# Digital_Input_Board.net
KiCad netlist of a schematic drawn in EAGLE
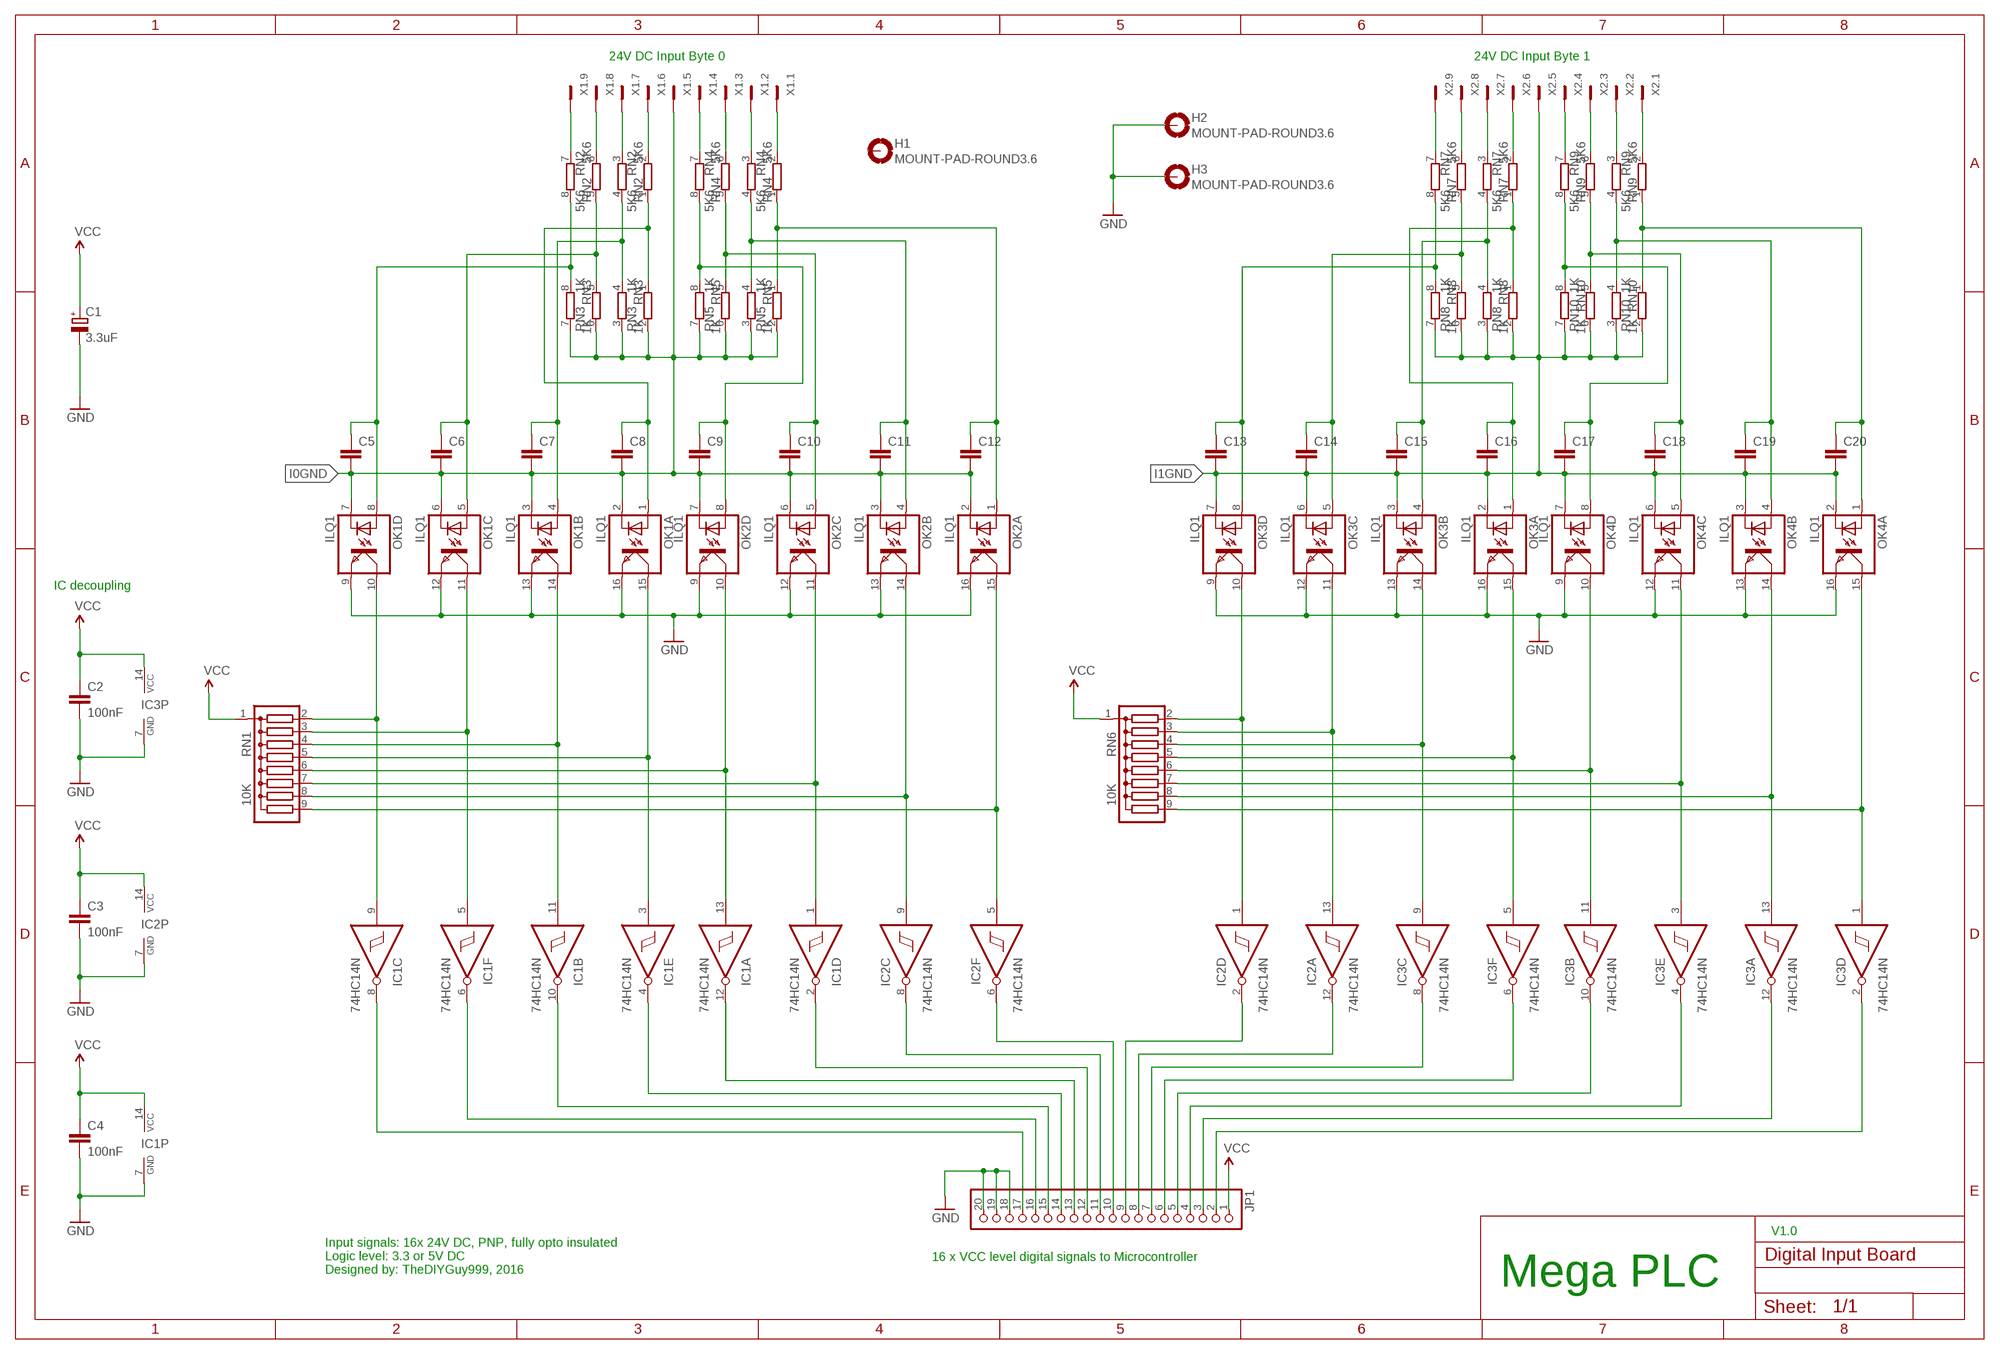
[diagram p0: schematic, sheet 1]

(export (version "E")
  (design (tool "Eeschema 10.0.6"))
  (components
    (comp (ref "C1")
      (value "3.3uF")
      (footprint "eagle-import:B45181A")
      (libsource (lib "eagle-import") (part "CPOL-EUB45181A"))
    )
    (comp (ref "C2")
      (value "100nF")
      (footprint "eagle-import:C025-024X044")
      (libsource (lib "eagle-import") (part "resistor_C-EU025-024X044"))
    )
    (comp (ref "C3")
      (value "100nF")
      (footprint "eagle-import:C025-024X044")
      (libsource (lib "eagle-import") (part "resistor_C-EU025-024X044"))
    )
    (comp (ref "C4")
      (value "100nF")
      (footprint "eagle-import:C025-024X044")
      (libsource (lib "eagle-import") (part "resistor_C-EU025-024X044"))
    )
    (comp (ref "C5")
      (value "C-EUC0805K")
      (footprint "eagle-import:C0805K")
      (libsource (lib "eagle-import") (part "C-EUC0805K"))
    )
    (comp (ref "C6")
      (value "C-EUC0805K")
      (footprint "eagle-import:C0805K")
      (libsource (lib "eagle-import") (part "C-EUC0805K"))
    )
    (comp (ref "C7")
      (value "C-EUC0805K")
      (footprint "eagle-import:C0805K")
      (libsource (lib "eagle-import") (part "C-EUC0805K"))
    )
    (comp (ref "C8")
      (value "C-EUC0805K")
      (footprint "eagle-import:C0805K")
      (libsource (lib "eagle-import") (part "C-EUC0805K"))
    )
    (comp (ref "C9")
      (value "C-EUC0805K")
      (footprint "eagle-import:C0805K")
      (libsource (lib "eagle-import") (part "C-EUC0805K"))
    )
    (comp (ref "C10")
      (value "C-EUC0805K")
      (footprint "eagle-import:C0805K")
      (libsource (lib "eagle-import") (part "C-EUC0805K"))
    )
    (comp (ref "C11")
      (value "C-EUC0805K")
      (footprint "eagle-import:C0805K")
      (libsource (lib "eagle-import") (part "C-EUC0805K"))
    )
    (comp (ref "C12")
      (value "C-EUC0805K")
      (footprint "eagle-import:C0805K")
      (libsource (lib "eagle-import") (part "C-EUC0805K"))
    )
    (comp (ref "C13")
      (value "C-EUC0805K")
      (footprint "eagle-import:C0805K")
      (libsource (lib "eagle-import") (part "C-EUC0805K"))
    )
    (comp (ref "C14")
      (value "C-EUC0805K")
      (footprint "eagle-import:C0805K")
      (libsource (lib "eagle-import") (part "C-EUC0805K"))
    )
    (comp (ref "C15")
      (value "C-EUC0805K")
      (footprint "eagle-import:C0805K")
      (libsource (lib "eagle-import") (part "C-EUC0805K"))
    )
    (comp (ref "C16")
      (value "C-EUC0805K")
      (footprint "eagle-import:C0805K")
      (libsource (lib "eagle-import") (part "C-EUC0805K"))
    )
    (comp (ref "C17")
      (value "C-EUC0805K")
      (footprint "eagle-import:C0805K")
      (libsource (lib "eagle-import") (part "C-EUC0805K"))
    )
    (comp (ref "C18")
      (value "C-EUC0805K")
      (footprint "eagle-import:C0805K")
      (libsource (lib "eagle-import") (part "C-EUC0805K"))
    )
    (comp (ref "C19")
      (value "C-EUC0805K")
      (footprint "eagle-import:C0805K")
      (libsource (lib "eagle-import") (part "C-EUC0805K"))
    )
    (comp (ref "C20")
      (value "C-EUC0805K")
      (footprint "eagle-import:C0805K")
      (libsource (lib "eagle-import") (part "C-EUC0805K"))
    )
    (comp (ref "H1")
      (value "MOUNT-PAD-ROUND3.6")
      (footprint "eagle-import:3,6-PAD")
      (libsource (lib "eagle-import") (part "MOUNT-PAD-ROUND3.6"))
    )
    (comp (ref "H2")
      (value "MOUNT-PAD-ROUND3.6")
      (footprint "eagle-import:3,6-PAD")
      (libsource (lib "eagle-import") (part "MOUNT-PAD-ROUND3.6"))
    )
    (comp (ref "H3")
      (value "MOUNT-PAD-ROUND3.6")
      (footprint "eagle-import:3,6-PAD")
      (libsource (lib "eagle-import") (part "MOUNT-PAD-ROUND3.6"))
    )
    (comp (ref "IC1")
      (value "74HC14N")
      (footprint "eagle-import:DIL14")
      (libsource (lib "eagle-import") (part "7414NHC"))
    )
    (comp (ref "IC2")
      (value "74HC14N")
      (footprint "eagle-import:DIL14")
      (libsource (lib "eagle-import") (part "7414NHC"))
    )
    (comp (ref "IC3")
      (value "74HC14N")
      (footprint "eagle-import:DIL14")
      (libsource (lib "eagle-import") (part "7414NHC"))
    )
    (comp (ref "JP1")
      (value "PINHD-1X20/90")
      (footprint "eagle-import:1X20_90")
      (libsource (lib "eagle-import") (part "PINHD-1X20/90"))
    )
    (comp (ref "OK1")
      (value "ILQ1")
      (footprint "eagle-import:DIL16")
      (fields (field (name "MF") "VISHAY/TELEFUNKEN"))
      (libsource (lib "eagle-import") (part "ILQ1"))
    )
    (comp (ref "OK2")
      (value "ILQ1")
      (footprint "eagle-import:DIL16")
      (fields (field (name "MF") "VISHAY/TELEFUNKEN"))
      (libsource (lib "eagle-import") (part "ILQ1"))
    )
    (comp (ref "OK3")
      (value "ILQ1")
      (footprint "eagle-import:DIL16")
      (fields (field (name "MF") "VISHAY/TELEFUNKEN"))
      (libsource (lib "eagle-import") (part "ILQ1"))
    )
    (comp (ref "OK4")
      (value "ILQ1")
      (footprint "eagle-import:DIL16")
      (fields (field (name "MF") "VISHAY/TELEFUNKEN"))
      (libsource (lib "eagle-import") (part "ILQ1"))
    )
    (comp (ref "RN1")
      (value "10K")
      (footprint "eagle-import:SIL9")
      (libsource (lib "eagle-import") (part "G08R"))
    )
    (comp (ref "RN2")
      (value "5K6")
      (footprint "eagle-import:SIL8")
      (libsource (lib "eagle-import") (part "E4RP"))
    )
    (comp (ref "RN3")
      (value "1K")
      (footprint "eagle-import:SIL8")
      (libsource (lib "eagle-import") (part "E4RP"))
    )
    (comp (ref "RN4")
      (value "5K6")
      (footprint "eagle-import:SIL8")
      (libsource (lib "eagle-import") (part "E4RP"))
    )
    (comp (ref "RN5")
      (value "1K")
      (footprint "eagle-import:SIL8")
      (libsource (lib "eagle-import") (part "E4RP"))
    )
    (comp (ref "RN6")
      (value "10K")
      (footprint "eagle-import:SIL9")
      (libsource (lib "eagle-import") (part "G08R"))
    )
    (comp (ref "RN7")
      (value "5K6")
      (footprint "eagle-import:SIL8")
      (libsource (lib "eagle-import") (part "E4RP"))
    )
    (comp (ref "RN8")
      (value "1K")
      (footprint "eagle-import:SIL8")
      (libsource (lib "eagle-import") (part "E4RP"))
    )
    (comp (ref "RN9")
      (value "5K6")
      (footprint "eagle-import:SIL8")
      (libsource (lib "eagle-import") (part "E4RP"))
    )
    (comp (ref "RN10")
      (value "1K")
      (footprint "eagle-import:SIL8")
      (libsource (lib "eagle-import") (part "E4RP"))
    )
    (comp (ref "X1")
      (value "MC9")
      (footprint "eagle-import:MC9")
      (libsource (lib "eagle-import") (part "MC9"))
    )
    (comp (ref "X2")
      (value "MC9")
      (footprint "eagle-import:MC9")
      (libsource (lib "eagle-import") (part "MC9"))
    )
  )
  (nets
    (net (code "1") (name "GND") (class "Default")
      (node (ref "C1") (pin "-") (pinfunction "-_-") (pintype "passive"))
      (node (ref "C2") (pin "2") (pinfunction "2_2") (pintype "passive"))
      (node (ref "C3") (pin "2") (pinfunction "2_2") (pintype "passive"))
      (node (ref "C4") (pin "2") (pinfunction "2_2") (pintype "passive"))
      (node (ref "H2") (pin "B3,6") (pinfunction "MOUNT_B3,6") (pintype "passive"))
      (node (ref "H3") (pin "B3,6") (pinfunction "MOUNT_B3,6") (pintype "passive"))
      (node (ref "IC1") (pin "7") (pinfunction "GND_7") (pintype "power_in"))
      (node (ref "IC2") (pin "7") (pinfunction "GND_7") (pintype "power_in"))
      (node (ref "IC3") (pin "7") (pinfunction "GND_7") (pintype "power_in"))
      (node (ref "JP1") (pin "18") (pinfunction "18_18") (pintype "passive"))
      (node (ref "JP1") (pin "19") (pinfunction "19_19") (pintype "passive"))
      (node (ref "JP1") (pin "20") (pinfunction "20_20") (pintype "passive"))
      (node (ref "OK1") (pin "12") (pinfunction "EMIT_12") (pintype "passive"))
      (node (ref "OK1") (pin "13") (pinfunction "EMIT_13") (pintype "passive"))
      (node (ref "OK1") (pin "16") (pinfunction "EMIT_16") (pintype "passive"))
      (node (ref "OK1") (pin "9") (pinfunction "EMIT_9") (pintype "passive"))
      (node (ref "OK2") (pin "12") (pinfunction "EMIT_12") (pintype "passive"))
      (node (ref "OK2") (pin "13") (pinfunction "EMIT_13") (pintype "passive"))
      (node (ref "OK2") (pin "16") (pinfunction "EMIT_16") (pintype "passive"))
      (node (ref "OK2") (pin "9") (pinfunction "EMIT_9") (pintype "passive"))
      (node (ref "OK3") (pin "12") (pinfunction "EMIT_12") (pintype "passive"))
      (node (ref "OK3") (pin "13") (pinfunction "EMIT_13") (pintype "passive"))
      (node (ref "OK3") (pin "16") (pinfunction "EMIT_16") (pintype "passive"))
      (node (ref "OK3") (pin "9") (pinfunction "EMIT_9") (pintype "passive"))
      (node (ref "OK4") (pin "12") (pinfunction "EMIT_12") (pintype "passive"))
      (node (ref "OK4") (pin "13") (pinfunction "EMIT_13") (pintype "passive"))
      (node (ref "OK4") (pin "16") (pinfunction "EMIT_16") (pintype "passive"))
      (node (ref "OK4") (pin "9") (pinfunction "EMIT_9") (pintype "passive"))
    )
    (net (code "2") (name "I0GND") (class "Default")
      (node (ref "C10") (pin "2") (pinfunction "2_2") (pintype "passive"))
      (node (ref "C11") (pin "2") (pinfunction "2_2") (pintype "passive"))
      (node (ref "C12") (pin "2") (pinfunction "2_2") (pintype "passive"))
      (node (ref "C5") (pin "2") (pinfunction "2_2") (pintype "passive"))
      (node (ref "C6") (pin "2") (pinfunction "2_2") (pintype "passive"))
      (node (ref "C7") (pin "2") (pinfunction "2_2") (pintype "passive"))
      (node (ref "C8") (pin "2") (pinfunction "2_2") (pintype "passive"))
      (node (ref "C9") (pin "2") (pinfunction "2_2") (pintype "passive"))
      (node (ref "OK1") (pin "2") (pinfunction "C_2") (pintype "passive"))
      (node (ref "OK1") (pin "3") (pinfunction "C_3") (pintype "passive"))
      (node (ref "OK1") (pin "6") (pinfunction "C_6") (pintype "passive"))
      (node (ref "OK1") (pin "7") (pinfunction "C_7") (pintype "passive"))
      (node (ref "OK2") (pin "2") (pinfunction "C_2") (pintype "passive"))
      (node (ref "OK2") (pin "3") (pinfunction "C_3") (pintype "passive"))
      (node (ref "OK2") (pin "6") (pinfunction "C_6") (pintype "passive"))
      (node (ref "OK2") (pin "7") (pinfunction "C_7") (pintype "passive"))
      (node (ref "RN3") (pin "2") (pinfunction "2_2") (pintype "passive"))
      (node (ref "RN3") (pin "3") (pinfunction "1_3") (pintype "passive"))
      (node (ref "RN3") (pin "6") (pinfunction "2_6") (pintype "passive"))
      (node (ref "RN3") (pin "7") (pinfunction "1_7") (pintype "passive"))
      (node (ref "RN5") (pin "2") (pinfunction "2_2") (pintype "passive"))
      (node (ref "RN5") (pin "3") (pinfunction "1_3") (pintype "passive"))
      (node (ref "RN5") (pin "6") (pinfunction "2_6") (pintype "passive"))
      (node (ref "RN5") (pin "7") (pinfunction "1_7") (pintype "passive"))
      (node (ref "X1") (pin "5") (pinfunction "SK_5") (pintype "passive"))
    )
    (net (code "3") (name "I1GND") (class "Default")
      (node (ref "C13") (pin "2") (pinfunction "2_2") (pintype "passive"))
      (node (ref "C14") (pin "2") (pinfunction "2_2") (pintype "passive"))
      (node (ref "C15") (pin "2") (pinfunction "2_2") (pintype "passive"))
      (node (ref "C16") (pin "2") (pinfunction "2_2") (pintype "passive"))
      (node (ref "C17") (pin "2") (pinfunction "2_2") (pintype "passive"))
      (node (ref "C18") (pin "2") (pinfunction "2_2") (pintype "passive"))
      (node (ref "C19") (pin "2") (pinfunction "2_2") (pintype "passive"))
      (node (ref "C20") (pin "2") (pinfunction "2_2") (pintype "passive"))
      (node (ref "OK3") (pin "2") (pinfunction "C_2") (pintype "passive"))
      (node (ref "OK3") (pin "3") (pinfunction "C_3") (pintype "passive"))
      (node (ref "OK3") (pin "6") (pinfunction "C_6") (pintype "passive"))
      (node (ref "OK3") (pin "7") (pinfunction "C_7") (pintype "passive"))
      (node (ref "OK4") (pin "2") (pinfunction "C_2") (pintype "passive"))
      (node (ref "OK4") (pin "3") (pinfunction "C_3") (pintype "passive"))
      (node (ref "OK4") (pin "6") (pinfunction "C_6") (pintype "passive"))
      (node (ref "OK4") (pin "7") (pinfunction "C_7") (pintype "passive"))
      (node (ref "RN10") (pin "2") (pinfunction "2_2") (pintype "passive"))
      (node (ref "RN10") (pin "3") (pinfunction "1_3") (pintype "passive"))
      (node (ref "RN10") (pin "6") (pinfunction "2_6") (pintype "passive"))
      (node (ref "RN10") (pin "7") (pinfunction "1_7") (pintype "passive"))
      (node (ref "RN8") (pin "2") (pinfunction "2_2") (pintype "passive"))
      (node (ref "RN8") (pin "3") (pinfunction "1_3") (pintype "passive"))
      (node (ref "RN8") (pin "6") (pinfunction "2_6") (pintype "passive"))
      (node (ref "RN8") (pin "7") (pinfunction "1_7") (pintype "passive"))
      (node (ref "X2") (pin "5") (pinfunction "SK_5") (pintype "passive"))
    )
    (net (code "4") (name "Net-(IC1A-I)") (class "Default")
      (node (ref "IC1") (pin "13") (pinfunction "I_13") (pintype "input"))
      (node (ref "OK2") (pin "10") (pinfunction "COL_10") (pintype "passive"))
      (node (ref "RN1") (pin "6") (pinfunction "6_6") (pintype "passive"))
    )
    (net (code "5") (name "Net-(IC1A-O)") (class "Default")
      (node (ref "IC1") (pin "12") (pinfunction "O_12") (pintype "output"))
      (node (ref "JP1") (pin "13") (pinfunction "13_13") (pintype "passive"))
    )
    (net (code "6") (name "Net-(IC1B-I)") (class "Default")
      (node (ref "IC1") (pin "11") (pinfunction "I_11") (pintype "input"))
      (node (ref "OK1") (pin "14") (pinfunction "COL_14") (pintype "passive"))
      (node (ref "RN1") (pin "4") (pinfunction "4_4") (pintype "passive"))
    )
    (net (code "7") (name "Net-(IC1B-O)") (class "Default")
      (node (ref "IC1") (pin "10") (pinfunction "O_10") (pintype "output"))
      (node (ref "JP1") (pin "15") (pinfunction "15_15") (pintype "passive"))
    )
    (net (code "8") (name "Net-(IC1C-I)") (class "Default")
      (node (ref "IC1") (pin "9") (pinfunction "I_9") (pintype "input"))
      (node (ref "OK1") (pin "10") (pinfunction "COL_10") (pintype "passive"))
      (node (ref "RN1") (pin "2") (pinfunction "2_2") (pintype "passive"))
    )
    (net (code "9") (name "Net-(IC1C-O)") (class "Default")
      (node (ref "IC1") (pin "8") (pinfunction "O_8") (pintype "output"))
      (node (ref "JP1") (pin "17") (pinfunction "17_17") (pintype "passive"))
    )
    (net (code "10") (name "Net-(IC1D-I)") (class "Default")
      (node (ref "IC1") (pin "1") (pinfunction "I_1") (pintype "input"))
      (node (ref "OK2") (pin "11") (pinfunction "COL_11") (pintype "passive"))
      (node (ref "RN1") (pin "7") (pinfunction "7_7") (pintype "passive"))
    )
    (net (code "11") (name "Net-(IC1D-O)") (class "Default")
      (node (ref "IC1") (pin "2") (pinfunction "O_2") (pintype "output"))
      (node (ref "JP1") (pin "12") (pinfunction "12_12") (pintype "passive"))
    )
    (net (code "12") (name "Net-(IC1E-I)") (class "Default")
      (node (ref "IC1") (pin "3") (pinfunction "I_3") (pintype "input"))
      (node (ref "OK1") (pin "15") (pinfunction "COL_15") (pintype "passive"))
      (node (ref "RN1") (pin "5") (pinfunction "5_5") (pintype "passive"))
    )
    (net (code "13") (name "Net-(IC1E-O)") (class "Default")
      (node (ref "IC1") (pin "4") (pinfunction "O_4") (pintype "output"))
      (node (ref "JP1") (pin "14") (pinfunction "14_14") (pintype "passive"))
    )
    (net (code "14") (name "Net-(IC1F-I)") (class "Default")
      (node (ref "IC1") (pin "5") (pinfunction "I_5") (pintype "input"))
      (node (ref "OK1") (pin "11") (pinfunction "COL_11") (pintype "passive"))
      (node (ref "RN1") (pin "3") (pinfunction "3_3") (pintype "passive"))
    )
    (net (code "15") (name "Net-(IC1F-O)") (class "Default")
      (node (ref "IC1") (pin "6") (pinfunction "O_6") (pintype "output"))
      (node (ref "JP1") (pin "16") (pinfunction "16_16") (pintype "passive"))
    )
    (net (code "16") (name "Net-(IC2A-I)") (class "Default")
      (node (ref "IC2") (pin "13") (pinfunction "I_13") (pintype "input"))
      (node (ref "OK3") (pin "11") (pinfunction "COL_11") (pintype "passive"))
      (node (ref "RN6") (pin "3") (pinfunction "3_3") (pintype "passive"))
    )
    (net (code "17") (name "Net-(IC2A-O)") (class "Default")
      (node (ref "IC2") (pin "12") (pinfunction "O_12") (pintype "output"))
      (node (ref "JP1") (pin "8") (pinfunction "8_8") (pintype "passive"))
    )
    (net (code "18") (name "Net-(IC2C-I)") (class "Default")
      (node (ref "IC2") (pin "9") (pinfunction "I_9") (pintype "input"))
      (node (ref "OK2") (pin "14") (pinfunction "COL_14") (pintype "passive"))
      (node (ref "RN1") (pin "8") (pinfunction "8_8") (pintype "passive"))
    )
    (net (code "19") (name "Net-(IC2C-O)") (class "Default")
      (node (ref "IC2") (pin "8") (pinfunction "O_8") (pintype "output"))
      (node (ref "JP1") (pin "11") (pinfunction "11_11") (pintype "passive"))
    )
    (net (code "20") (name "Net-(IC2D-I)") (class "Default")
      (node (ref "IC2") (pin "1") (pinfunction "I_1") (pintype "input"))
      (node (ref "OK3") (pin "10") (pinfunction "COL_10") (pintype "passive"))
      (node (ref "RN6") (pin "2") (pinfunction "2_2") (pintype "passive"))
    )
    (net (code "21") (name "Net-(IC2D-O)") (class "Default")
      (node (ref "IC2") (pin "2") (pinfunction "O_2") (pintype "output"))
      (node (ref "JP1") (pin "9") (pinfunction "9_9") (pintype "passive"))
    )
    (net (code "22") (name "Net-(IC2F-I)") (class "Default")
      (node (ref "IC2") (pin "5") (pinfunction "I_5") (pintype "input"))
      (node (ref "OK2") (pin "15") (pinfunction "COL_15") (pintype "passive"))
      (node (ref "RN1") (pin "9") (pinfunction "9_9") (pintype "passive"))
    )
    (net (code "23") (name "Net-(IC2F-O)") (class "Default")
      (node (ref "IC2") (pin "6") (pinfunction "O_6") (pintype "output"))
      (node (ref "JP1") (pin "10") (pinfunction "10_10") (pintype "passive"))
    )
    (net (code "24") (name "Net-(IC3A-I)") (class "Default")
      (node (ref "IC3") (pin "13") (pinfunction "I_13") (pintype "input"))
      (node (ref "OK4") (pin "14") (pinfunction "COL_14") (pintype "passive"))
      (node (ref "RN6") (pin "8") (pinfunction "8_8") (pintype "passive"))
    )
    (net (code "25") (name "Net-(IC3A-O)") (class "Default")
      (node (ref "IC3") (pin "12") (pinfunction "O_12") (pintype "output"))
      (node (ref "JP1") (pin "3") (pinfunction "3_3") (pintype "passive"))
    )
    (net (code "26") (name "Net-(IC3B-I)") (class "Default")
      (node (ref "IC3") (pin "11") (pinfunction "I_11") (pintype "input"))
      (node (ref "OK4") (pin "10") (pinfunction "COL_10") (pintype "passive"))
      (node (ref "RN6") (pin "6") (pinfunction "6_6") (pintype "passive"))
    )
    (net (code "27") (name "Net-(IC3B-O)") (class "Default")
      (node (ref "IC3") (pin "10") (pinfunction "O_10") (pintype "output"))
      (node (ref "JP1") (pin "5") (pinfunction "5_5") (pintype "passive"))
    )
    (net (code "28") (name "Net-(IC3C-I)") (class "Default")
      (node (ref "IC3") (pin "9") (pinfunction "I_9") (pintype "input"))
      (node (ref "OK3") (pin "14") (pinfunction "COL_14") (pintype "passive"))
      (node (ref "RN6") (pin "4") (pinfunction "4_4") (pintype "passive"))
    )
    (net (code "29") (name "Net-(IC3C-O)") (class "Default")
      (node (ref "IC3") (pin "8") (pinfunction "O_8") (pintype "output"))
      (node (ref "JP1") (pin "7") (pinfunction "7_7") (pintype "passive"))
    )
    (net (code "30") (name "Net-(IC3D-I)") (class "Default")
      (node (ref "IC3") (pin "1") (pinfunction "I_1") (pintype "input"))
      (node (ref "OK4") (pin "15") (pinfunction "COL_15") (pintype "passive"))
      (node (ref "RN6") (pin "9") (pinfunction "9_9") (pintype "passive"))
    )
    (net (code "31") (name "Net-(IC3D-O)") (class "Default")
      (node (ref "IC3") (pin "2") (pinfunction "O_2") (pintype "output"))
      (node (ref "JP1") (pin "2") (pinfunction "2_2") (pintype "passive"))
    )
    (net (code "32") (name "Net-(IC3E-I)") (class "Default")
      (node (ref "IC3") (pin "3") (pinfunction "I_3") (pintype "input"))
      (node (ref "OK4") (pin "11") (pinfunction "COL_11") (pintype "passive"))
      (node (ref "RN6") (pin "7") (pinfunction "7_7") (pintype "passive"))
    )
    (net (code "33") (name "Net-(IC3E-O)") (class "Default")
      (node (ref "IC3") (pin "4") (pinfunction "O_4") (pintype "output"))
      (node (ref "JP1") (pin "4") (pinfunction "4_4") (pintype "passive"))
    )
    (net (code "34") (name "Net-(IC3F-I)") (class "Default")
      (node (ref "IC3") (pin "5") (pinfunction "I_5") (pintype "input"))
      (node (ref "OK3") (pin "15") (pinfunction "COL_15") (pintype "passive"))
      (node (ref "RN6") (pin "5") (pinfunction "5_5") (pintype "passive"))
    )
    (net (code "35") (name "Net-(IC3F-O)") (class "Default")
      (node (ref "IC3") (pin "6") (pinfunction "O_6") (pintype "output"))
      (node (ref "JP1") (pin "6") (pinfunction "6_6") (pintype "passive"))
    )
    (net (code "36") (name "Net-(OK1A-A)") (class "Default")
      (node (ref "C8") (pin "1") (pinfunction "1_1") (pintype "passive"))
      (node (ref "OK1") (pin "1") (pinfunction "A_1") (pintype "passive"))
      (node (ref "RN2") (pin "1") (pinfunction "1_1") (pintype "passive"))
      (node (ref "RN3") (pin "1") (pinfunction "1_1") (pintype "passive"))
    )
    (net (code "37") (name "Net-(OK1B-A)") (class "Default")
      (node (ref "C7") (pin "1") (pinfunction "1_1") (pintype "passive"))
      (node (ref "OK1") (pin "4") (pinfunction "A_4") (pintype "passive"))
      (node (ref "RN2") (pin "4") (pinfunction "2_4") (pintype "passive"))
      (node (ref "RN3") (pin "4") (pinfunction "2_4") (pintype "passive"))
    )
    (net (code "38") (name "Net-(OK1C-A)") (class "Default")
      (node (ref "C6") (pin "1") (pinfunction "1_1") (pintype "passive"))
      (node (ref "OK1") (pin "5") (pinfunction "A_5") (pintype "passive"))
      (node (ref "RN2") (pin "5") (pinfunction "1_5") (pintype "passive"))
      (node (ref "RN3") (pin "5") (pinfunction "1_5") (pintype "passive"))
    )
    (net (code "39") (name "Net-(OK1D-A)") (class "Default")
      (node (ref "C5") (pin "1") (pinfunction "1_1") (pintype "passive"))
      (node (ref "OK1") (pin "8") (pinfunction "A_8") (pintype "passive"))
      (node (ref "RN2") (pin "8") (pinfunction "2_8") (pintype "passive"))
      (node (ref "RN3") (pin "8") (pinfunction "2_8") (pintype "passive"))
    )
    (net (code "40") (name "Net-(OK2A-A)") (class "Default")
      (node (ref "C12") (pin "1") (pinfunction "1_1") (pintype "passive"))
      (node (ref "OK2") (pin "1") (pinfunction "A_1") (pintype "passive"))
      (node (ref "RN4") (pin "1") (pinfunction "1_1") (pintype "passive"))
      (node (ref "RN5") (pin "1") (pinfunction "1_1") (pintype "passive"))
    )
    (net (code "41") (name "Net-(OK2B-A)") (class "Default")
      (node (ref "C11") (pin "1") (pinfunction "1_1") (pintype "passive"))
      (node (ref "OK2") (pin "4") (pinfunction "A_4") (pintype "passive"))
      (node (ref "RN4") (pin "4") (pinfunction "2_4") (pintype "passive"))
      (node (ref "RN5") (pin "4") (pinfunction "2_4") (pintype "passive"))
    )
    (net (code "42") (name "Net-(OK2C-A)") (class "Default")
      (node (ref "C10") (pin "1") (pinfunction "1_1") (pintype "passive"))
      (node (ref "OK2") (pin "5") (pinfunction "A_5") (pintype "passive"))
      (node (ref "RN4") (pin "5") (pinfunction "1_5") (pintype "passive"))
      (node (ref "RN5") (pin "5") (pinfunction "1_5") (pintype "passive"))
    )
    (net (code "43") (name "Net-(OK2D-A)") (class "Default")
      (node (ref "C9") (pin "1") (pinfunction "1_1") (pintype "passive"))
      (node (ref "OK2") (pin "8") (pinfunction "A_8") (pintype "passive"))
      (node (ref "RN4") (pin "8") (pinfunction "2_8") (pintype "passive"))
      (node (ref "RN5") (pin "8") (pinfunction "2_8") (pintype "passive"))
    )
    (net (code "44") (name "Net-(OK3A-A)") (class "Default")
      (node (ref "C16") (pin "1") (pinfunction "1_1") (pintype "passive"))
      (node (ref "OK3") (pin "1") (pinfunction "A_1") (pintype "passive"))
      (node (ref "RN7") (pin "1") (pinfunction "1_1") (pintype "passive"))
      (node (ref "RN8") (pin "1") (pinfunction "1_1") (pintype "passive"))
    )
    (net (code "45") (name "Net-(OK3B-A)") (class "Default")
      (node (ref "C15") (pin "1") (pinfunction "1_1") (pintype "passive"))
      (node (ref "OK3") (pin "4") (pinfunction "A_4") (pintype "passive"))
      (node (ref "RN7") (pin "4") (pinfunction "2_4") (pintype "passive"))
      (node (ref "RN8") (pin "4") (pinfunction "2_4") (pintype "passive"))
    )
    (net (code "46") (name "Net-(OK3C-A)") (class "Default")
      (node (ref "C14") (pin "1") (pinfunction "1_1") (pintype "passive"))
      (node (ref "OK3") (pin "5") (pinfunction "A_5") (pintype "passive"))
      (node (ref "RN7") (pin "5") (pinfunction "1_5") (pintype "passive"))
      (node (ref "RN8") (pin "5") (pinfunction "1_5") (pintype "passive"))
    )
    (net (code "47") (name "Net-(OK3D-A)") (class "Default")
      (node (ref "C13") (pin "1") (pinfunction "1_1") (pintype "passive"))
      (node (ref "OK3") (pin "8") (pinfunction "A_8") (pintype "passive"))
      (node (ref "RN7") (pin "8") (pinfunction "2_8") (pintype "passive"))
      (node (ref "RN8") (pin "8") (pinfunction "2_8") (pintype "passive"))
    )
    (net (code "48") (name "Net-(OK4A-A)") (class "Default")
      (node (ref "C20") (pin "1") (pinfunction "1_1") (pintype "passive"))
      (node (ref "OK4") (pin "1") (pinfunction "A_1") (pintype "passive"))
      (node (ref "RN10") (pin "1") (pinfunction "1_1") (pintype "passive"))
      (node (ref "RN9") (pin "1") (pinfunction "1_1") (pintype "passive"))
    )
    (net (code "49") (name "Net-(OK4B-A)") (class "Default")
      (node (ref "C19") (pin "1") (pinfunction "1_1") (pintype "passive"))
      (node (ref "OK4") (pin "4") (pinfunction "A_4") (pintype "passive"))
      (node (ref "RN10") (pin "4") (pinfunction "2_4") (pintype "passive"))
      (node (ref "RN9") (pin "4") (pinfunction "2_4") (pintype "passive"))
    )
    (net (code "50") (name "Net-(OK4C-A)") (class "Default")
      (node (ref "C18") (pin "1") (pinfunction "1_1") (pintype "passive"))
      (node (ref "OK4") (pin "5") (pinfunction "A_5") (pintype "passive"))
      (node (ref "RN10") (pin "5") (pinfunction "1_5") (pintype "passive"))
      (node (ref "RN9") (pin "5") (pinfunction "1_5") (pintype "passive"))
    )
    (net (code "51") (name "Net-(OK4D-A)") (class "Default")
      (node (ref "C17") (pin "1") (pinfunction "1_1") (pintype "passive"))
      (node (ref "OK4") (pin "8") (pinfunction "A_8") (pintype "passive"))
      (node (ref "RN10") (pin "8") (pinfunction "2_8") (pintype "passive"))
      (node (ref "RN9") (pin "8") (pinfunction "2_8") (pintype "passive"))
    )
    (net (code "52") (name "Net-(RN2B-1)") (class "Default")
      (node (ref "RN2") (pin "3") (pinfunction "1_3") (pintype "passive"))
      (node (ref "X1") (pin "7") (pinfunction "SK_7") (pintype "passive"))
    )
    (net (code "53") (name "Net-(RN2C-2)") (class "Default")
      (node (ref "RN2") (pin "6") (pinfunction "2_6") (pintype "passive"))
      (node (ref "X1") (pin "8") (pinfunction "SK_8") (pintype "passive"))
    )
    (net (code "54") (name "Net-(RN2D-1)") (class "Default")
      (node (ref "RN2") (pin "7") (pinfunction "1_7") (pintype "passive"))
      (node (ref "X1") (pin "9") (pinfunction "SK_9") (pintype "passive"))
    )
    (net (code "55") (name "Net-(RN4B-1)") (class "Default")
      (node (ref "RN4") (pin "3") (pinfunction "1_3") (pintype "passive"))
      (node (ref "X1") (pin "2") (pinfunction "SK_2") (pintype "passive"))
    )
    (net (code "56") (name "Net-(RN4C-2)") (class "Default")
      (node (ref "RN4") (pin "6") (pinfunction "2_6") (pintype "passive"))
      (node (ref "X1") (pin "3") (pinfunction "SK_3") (pintype "passive"))
    )
    (net (code "57") (name "Net-(RN4D-1)") (class "Default")
      (node (ref "RN4") (pin "7") (pinfunction "1_7") (pintype "passive"))
      (node (ref "X1") (pin "4") (pinfunction "SK_4") (pintype "passive"))
    )
    (net (code "58") (name "Net-(RN7B-1)") (class "Default")
      (node (ref "RN7") (pin "3") (pinfunction "1_3") (pintype "passive"))
      (node (ref "X2") (pin "7") (pinfunction "SK_7") (pintype "passive"))
    )
    (net (code "59") (name "Net-(RN7C-2)") (class "Default")
      (node (ref "RN7") (pin "6") (pinfunction "2_6") (pintype "passive"))
      (node (ref "X2") (pin "8") (pinfunction "SK_8") (pintype "passive"))
    )
    (net (code "60") (name "Net-(RN7D-1)") (class "Default")
      (node (ref "RN7") (pin "7") (pinfunction "1_7") (pintype "passive"))
      (node (ref "X2") (pin "9") (pinfunction "SK_9") (pintype "passive"))
    )
    (net (code "61") (name "Net-(RN9B-1)") (class "Default")
      (node (ref "RN9") (pin "3") (pinfunction "1_3") (pintype "passive"))
      (node (ref "X2") (pin "2") (pinfunction "SK_2") (pintype "passive"))
    )
    (net (code "62") (name "Net-(RN9C-2)") (class "Default")
      (node (ref "RN9") (pin "6") (pinfunction "2_6") (pintype "passive"))
      (node (ref "X2") (pin "3") (pinfunction "SK_3") (pintype "passive"))
    )
    (net (code "63") (name "Net-(RN9D-1)") (class "Default")
      (node (ref "RN9") (pin "7") (pinfunction "1_7") (pintype "passive"))
      (node (ref "X2") (pin "4") (pinfunction "SK_4") (pintype "passive"))
    )
    (net (code "64") (name "Net-(X1A-SK)") (class "Default")
      (node (ref "RN4") (pin "2") (pinfunction "2_2") (pintype "passive"))
      (node (ref "X1") (pin "1") (pinfunction "SK_1") (pintype "passive"))
    )
    (net (code "65") (name "Net-(X1F-SK)") (class "Default")
      (node (ref "RN2") (pin "2") (pinfunction "2_2") (pintype "passive"))
      (node (ref "X1") (pin "6") (pinfunction "SK_6") (pintype "passive"))
    )
    (net (code "66") (name "Net-(X2A-SK)") (class "Default")
      (node (ref "RN9") (pin "2") (pinfunction "2_2") (pintype "passive"))
      (node (ref "X2") (pin "1") (pinfunction "SK_1") (pintype "passive"))
    )
    (net (code "67") (name "Net-(X2F-SK)") (class "Default")
      (node (ref "RN7") (pin "2") (pinfunction "2_2") (pintype "passive"))
      (node (ref "X2") (pin "6") (pinfunction "SK_6") (pintype "passive"))
    )
    (net (code "68") (name "VCC") (class "Default")
      (node (ref "C1") (pin "+") (pinfunction "+_+") (pintype "passive"))
      (node (ref "C2") (pin "1") (pinfunction "1_1") (pintype "passive"))
      (node (ref "C3") (pin "1") (pinfunction "1_1") (pintype "passive"))
      (node (ref "C4") (pin "1") (pinfunction "1_1") (pintype "passive"))
      (node (ref "IC1") (pin "14") (pinfunction "VCC_14") (pintype "power_in"))
      (node (ref "IC2") (pin "14") (pinfunction "VCC_14") (pintype "power_in"))
      (node (ref "IC3") (pin "14") (pinfunction "VCC_14") (pintype "power_in"))
      (node (ref "JP1") (pin "1") (pinfunction "1_1") (pintype "passive"))
      (node (ref "RN1") (pin "1") (pinfunction "1_1") (pintype "passive"))
      (node (ref "RN6") (pin "1") (pinfunction "1_1") (pintype "passive"))
    )
    (net (code "69") (name "unconnected-(H1-MOUNT-PadB3,6)") (class "Default")
      (node (ref "H1") (pin "B3,6") (pinfunction "MOUNT_B3,6") (pintype "passive"))
    )
  )
)
